# schematic.net
KiCad netlist of a schematic drawn in EAGLE
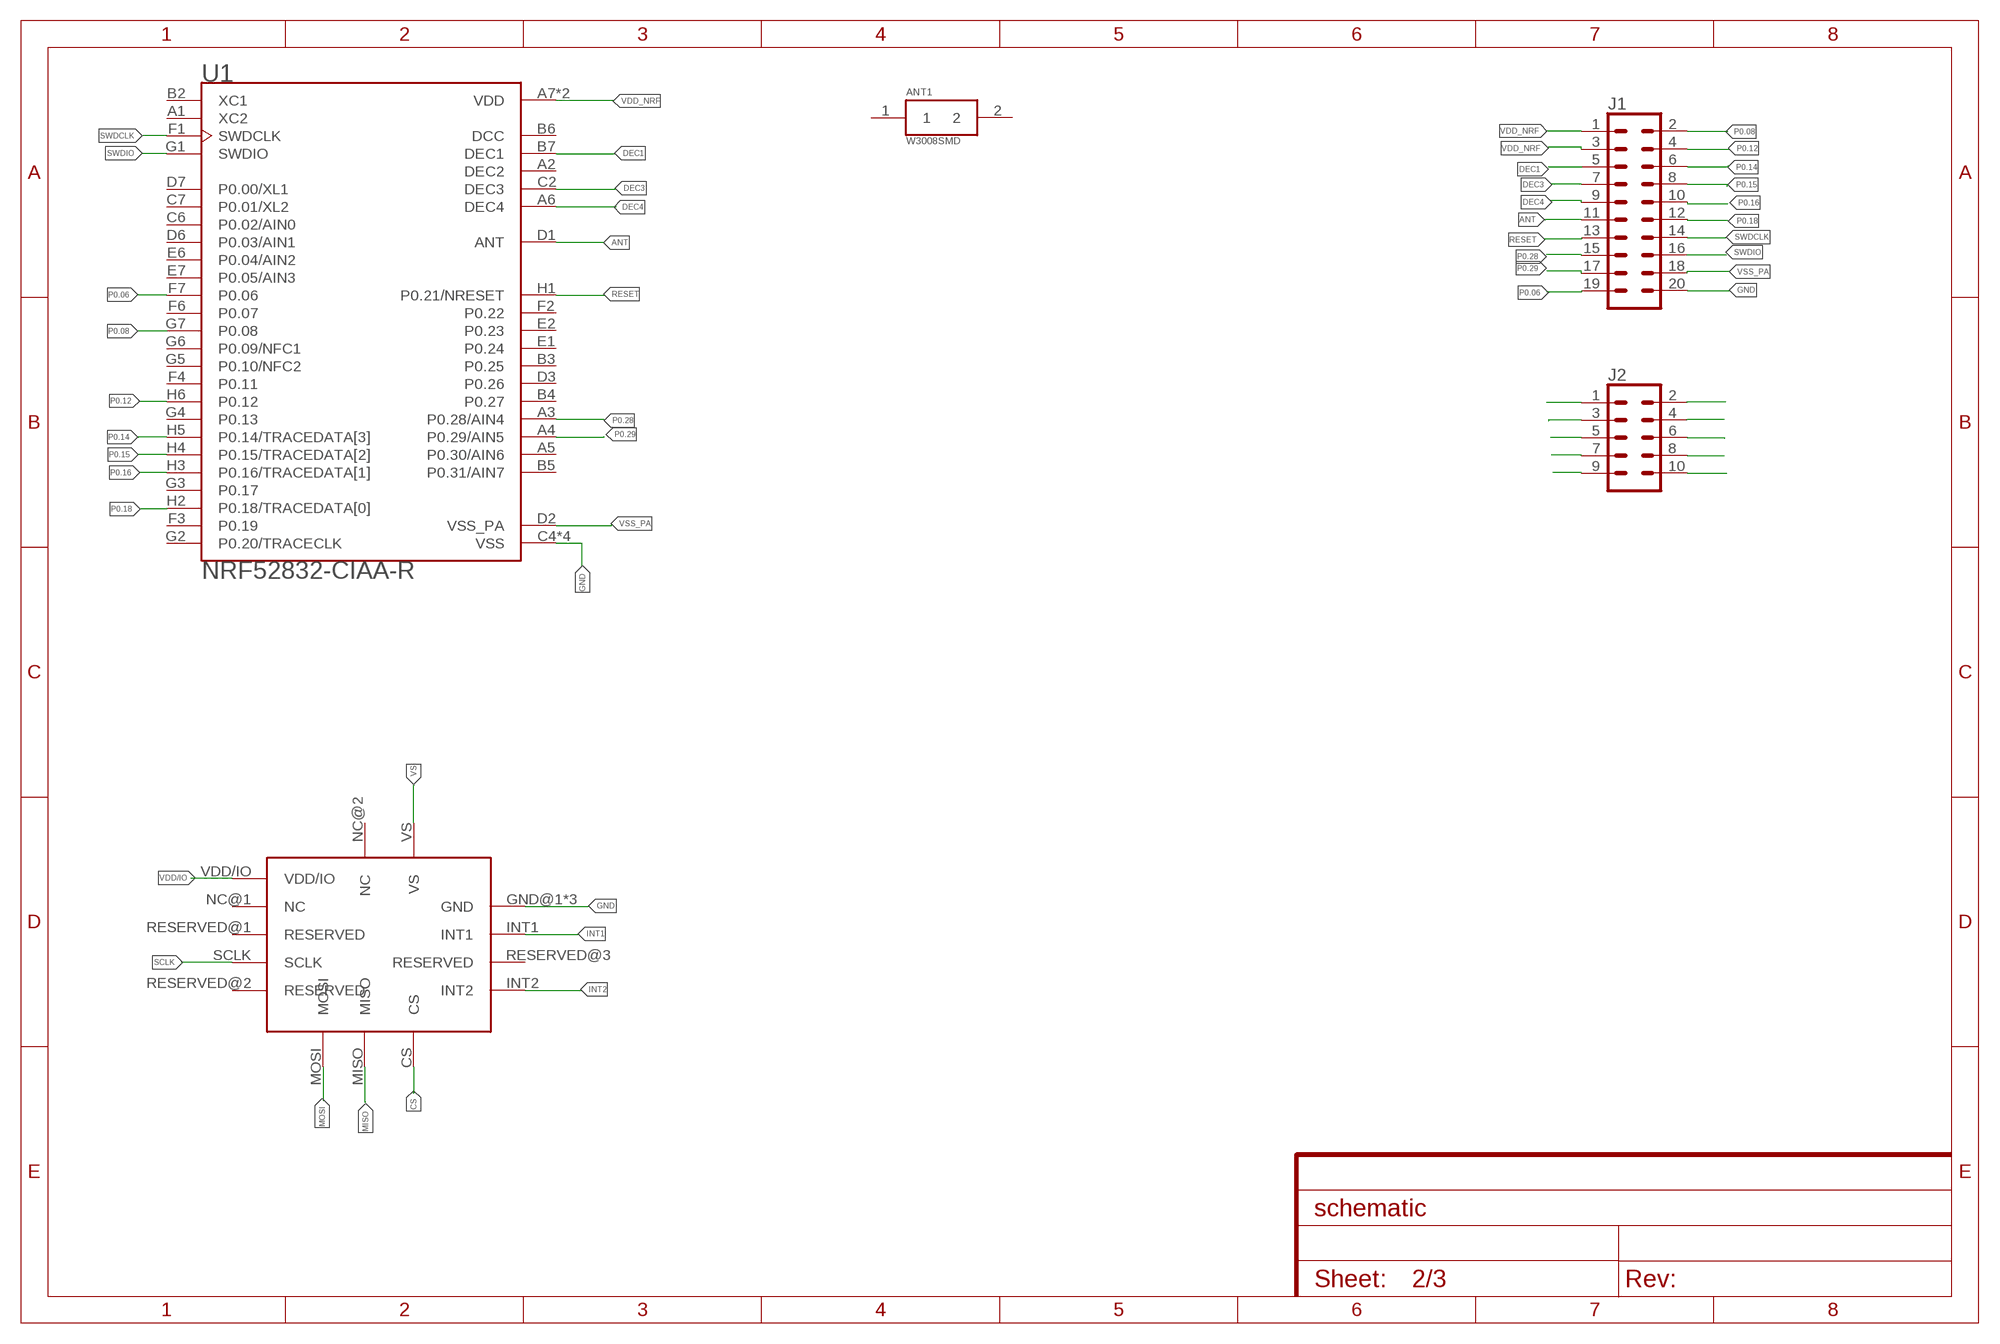
[diagram p0: schematic, sheet 2]

(export (version "E")
  (design (tool "Eeschema 10.0.6"))
  (components
    (comp (ref "ANT1")
      (value "W3008SMD")
      (footprint "eagle-import:_W3008")
      (fields (field (name "MF") "Pulse") (field (name "MP") "W3008"))
      (libsource (lib "eagle-import") (part "W3008SMD"))
    )
    (comp (ref "J1")
      (value "CONN_10X2")
      (footprint "eagle-import:2X10")
      (libsource (lib "eagle-import") (part "CONN_10X2"))
    )
    (comp (ref "J2")
      (value "CONN_05X20.05_IN_PTH_SILK")
      (footprint "eagle-import:2X5_PTH_SILK_.05")
      (libsource (lib "eagle-import") (part "CONN_05X20.05_IN_PTH_SILK"))
    )
    (comp (ref "U$1")
      (value "ADXL362")
      (footprint "eagle-import:TFLGA-16_3.3MMX3.1MM")
      (libsource (lib "eagle-import") (part "ADXL362"))
    )
    (comp (ref "U1")
      (value "NRF52832-CIAA-R")
      (footprint "eagle-import:BGA50N40P7X8_300X320X40")
      (fields (field (name "MF") "Nordic"))
      (libsource (lib "eagle-import") (part "NRF52832-CIAA-R"))
    )
  )
  (nets
    (net (code "1") (name "ANT") (class "Default")
      (node (ref "J1") (pin "11") (pinfunction "11_11") (pintype "passive"))
      (node (ref "U1") (pin "D1") (pinfunction "ANT_D1") (pintype "passive"))
    )
    (net (code "2") (name "CS") (class "Default")
      (node (ref "U$1") (pin "CS") (pinfunction "CS_CS") (pintype "bidirectional"))
    )
    (net (code "3") (name "DCC") (class "Default")
      (node (ref "U1") (pin "B6") (pinfunction "DCC_B6") (pintype "power_in"))
    )
    (net (code "4") (name "DEC1") (class "Default")
      (node (ref "J1") (pin "5") (pinfunction "5_5") (pintype "passive"))
      (node (ref "U1") (pin "B7") (pinfunction "DEC1_B7") (pintype "power_in"))
    )
    (net (code "5") (name "DEC2") (class "Default")
      (node (ref "U1") (pin "A2") (pinfunction "DEC2_A2") (pintype "power_in"))
    )
    (net (code "6") (name "DEC3") (class "Default")
      (node (ref "J1") (pin "7") (pinfunction "7_7") (pintype "passive"))
      (node (ref "U1") (pin "C2") (pinfunction "DEC3_C2") (pintype "power_in"))
    )
    (net (code "7") (name "DEC4") (class "Default")
      (node (ref "J1") (pin "9") (pinfunction "9_9") (pintype "passive"))
      (node (ref "U1") (pin "A6") (pinfunction "DEC4_A6") (pintype "power_in"))
    )
    (net (code "8") (name "GND") (class "Default")
      (node (ref "J1") (pin "20") (pinfunction "20_20") (pintype "passive"))
      (node (ref "U$1") (pin "GND@1") (pinfunction "GND_GND@1") (pintype "bidirectional"))
      (node (ref "U$1") (pin "GND@2") (pinfunction "GND_GND@2") (pintype "bidirectional"))
      (node (ref "U$1") (pin "GND@3") (pinfunction "GND_GND@3") (pintype "bidirectional"))
      (node (ref "U1") (pin "C4") (pinfunction "VSS_C4") (pintype "power_in"))
      (node (ref "U1") (pin "C5") (pinfunction "VSS_C5") (pintype "power_in"))
      (node (ref "U1") (pin "E3") (pinfunction "VSS_E3") (pintype "power_in"))
      (node (ref "U1") (pin "F5") (pinfunction "VSS_F5") (pintype "power_in"))
    )
    (net (code "9") (name "INT1") (class "Default")
      (node (ref "U$1") (pin "INT1") (pinfunction "INT1_INT1") (pintype "bidirectional"))
    )
    (net (code "10") (name "INT2") (class "Default")
      (node (ref "U$1") (pin "INT2") (pinfunction "INT2_INT2") (pintype "bidirectional"))
    )
    (net (code "11") (name "MISO") (class "Default")
      (node (ref "U$1") (pin "MISO") (pinfunction "MISO_MISO") (pintype "bidirectional"))
    )
    (net (code "12") (name "MOSI") (class "Default")
      (node (ref "U$1") (pin "MOSI") (pinfunction "MOSI_MOSI") (pintype "bidirectional"))
    )
    (net (code "13") (name "P0.06") (class "Default")
      (node (ref "J1") (pin "19") (pinfunction "19_19") (pintype "passive"))
      (node (ref "U1") (pin "F7") (pinfunction "P0.06_F7") (pintype "bidirectional"))
    )
    (net (code "14") (name "P0.08") (class "Default")
      (node (ref "J1") (pin "2") (pinfunction "2_2") (pintype "passive"))
      (node (ref "U1") (pin "G7") (pinfunction "P0.08_G7") (pintype "bidirectional"))
    )
    (net (code "15") (name "P0.12") (class "Default")
      (node (ref "J1") (pin "4") (pinfunction "4_4") (pintype "passive"))
      (node (ref "U1") (pin "H6") (pinfunction "P0.12_H6") (pintype "bidirectional"))
    )
    (net (code "16") (name "P0.14") (class "Default")
      (node (ref "J1") (pin "6") (pinfunction "6_6") (pintype "passive"))
      (node (ref "U1") (pin "H5") (pinfunction "P0.14/TRACEDATA[3]_H5") (pintype "bidirectional"))
    )
    (net (code "17") (name "P0.15") (class "Default")
      (node (ref "J1") (pin "8") (pinfunction "8_8") (pintype "passive"))
      (node (ref "U1") (pin "H4") (pinfunction "P0.15/TRACEDATA[2]_H4") (pintype "bidirectional"))
    )
    (net (code "18") (name "P0.16") (class "Default")
      (node (ref "J1") (pin "10") (pinfunction "10_10") (pintype "passive"))
      (node (ref "U1") (pin "H3") (pinfunction "P0.16/TRACEDATA[1]_H3") (pintype "bidirectional"))
    )
    (net (code "19") (name "P0.18") (class "Default")
      (node (ref "J1") (pin "12") (pinfunction "12_12") (pintype "passive"))
      (node (ref "U1") (pin "H2") (pinfunction "P0.18/TRACEDATA[0]_H2") (pintype "bidirectional"))
    )
    (net (code "20") (name "P0.28") (class "Default")
      (node (ref "J1") (pin "15") (pinfunction "15_15") (pintype "passive"))
      (node (ref "U1") (pin "A3") (pinfunction "P0.28/AIN4_A3") (pintype "bidirectional"))
    )
    (net (code "21") (name "P0.29") (class "Default")
      (node (ref "J1") (pin "17") (pinfunction "17_17") (pintype "passive"))
      (node (ref "U1") (pin "A4") (pinfunction "P0.29/AIN5_A4") (pintype "bidirectional"))
    )
    (net (code "22") (name "RESET") (class "Default")
      (node (ref "J1") (pin "13") (pinfunction "13_13") (pintype "passive"))
      (node (ref "U1") (pin "H1") (pinfunction "P0.21/NRESET_H1") (pintype "bidirectional"))
    )
    (net (code "23") (name "SCLK") (class "Default")
      (node (ref "U$1") (pin "SCLK") (pinfunction "SCLK_SCLK") (pintype "bidirectional"))
    )
    (net (code "24") (name "SWDCLK") (class "Default")
      (node (ref "J1") (pin "14") (pinfunction "14_14") (pintype "passive"))
      (node (ref "U1") (pin "F1") (pinfunction "SWDCLK_F1") (pintype "input"))
    )
    (net (code "25") (name "SWDIO") (class "Default")
      (node (ref "J1") (pin "16") (pinfunction "16_16") (pintype "passive"))
      (node (ref "U1") (pin "G1") (pinfunction "SWDIO_G1") (pintype "bidirectional"))
    )
    (net (code "26") (name "VDD_NRF") (class "Default")
      (node (ref "J1") (pin "1") (pinfunction "1_1") (pintype "passive"))
      (node (ref "J1") (pin "3") (pinfunction "3_3") (pintype "passive"))
      (node (ref "U1") (pin "A7") (pinfunction "VDD_A7") (pintype "power_in"))
      (node (ref "U1") (pin "H7") (pinfunction "VDD_H7") (pintype "power_in"))
    )
    (net (code "27") (name "VDD{slash}IO") (class "Default")
      (node (ref "U$1") (pin "VDD/IO") (pinfunction "VDD/IO_VDD/IO") (pintype "bidirectional"))
    )
    (net (code "28") (name "VS") (class "Default")
      (node (ref "U$1") (pin "VS") (pinfunction "VS_VS") (pintype "bidirectional"))
    )
    (net (code "29") (name "VSS_PA") (class "Default")
      (node (ref "J1") (pin "18") (pinfunction "18_18") (pintype "passive"))
      (node (ref "U1") (pin "D2") (pinfunction "VSS_PA_D2") (pintype "power_in"))
    )
    (net (code "30") (name "unconnected-(ANT1-Pad1)") (class "Default")
      (node (ref "ANT1") (pin "1") (pinfunction "1_1") (pintype "passive"))
    )
    (net (code "31") (name "unconnected-(ANT1-Pad2)") (class "Default")
      (node (ref "ANT1") (pin "2") (pinfunction "2_2") (pintype "passive"))
    )
    (net (code "32") (name "unconnected-(J2-Pad1)") (class "Default")
      (node (ref "J2") (pin "1") (pinfunction "1_1") (pintype "passive"))
    )
    (net (code "33") (name "unconnected-(J2-Pad2)") (class "Default")
      (node (ref "J2") (pin "2") (pinfunction "2_2") (pintype "passive"))
    )
    (net (code "34") (name "unconnected-(J2-Pad3)") (class "Default")
      (node (ref "J2") (pin "3") (pinfunction "3_3") (pintype "passive"))
    )
    (net (code "35") (name "unconnected-(J2-Pad4)") (class "Default")
      (node (ref "J2") (pin "4") (pinfunction "4_4") (pintype "passive"))
    )
    (net (code "36") (name "unconnected-(J2-Pad5)") (class "Default")
      (node (ref "J2") (pin "5") (pinfunction "5_5") (pintype "passive"))
    )
    (net (code "37") (name "unconnected-(J2-Pad6)") (class "Default")
      (node (ref "J2") (pin "6") (pinfunction "6_6") (pintype "passive"))
    )
    (net (code "38") (name "unconnected-(J2-Pad7)") (class "Default")
      (node (ref "J2") (pin "7") (pinfunction "7_7") (pintype "passive"))
    )
    (net (code "39") (name "unconnected-(J2-Pad8)") (class "Default")
      (node (ref "J2") (pin "8") (pinfunction "8_8") (pintype "passive"))
    )
    (net (code "40") (name "unconnected-(J2-Pad9)") (class "Default")
      (node (ref "J2") (pin "9") (pinfunction "9_9") (pintype "passive"))
    )
    (net (code "41") (name "unconnected-(J2-Pad10)") (class "Default")
      (node (ref "J2") (pin "10") (pinfunction "10_10") (pintype "passive"))
    )
    (net (code "42") (name "unconnected-(U$1-NC-PadNC@1)") (class "Default")
      (node (ref "U$1") (pin "NC@1") (pinfunction "NC_NC@1") (pintype "bidirectional"))
    )
    (net (code "43") (name "unconnected-(U$1-NC-PadNC@2)") (class "Default")
      (node (ref "U$1") (pin "NC@2") (pinfunction "NC_NC@2") (pintype "bidirectional"))
    )
    (net (code "44") (name "unconnected-(U$1-RESERVED-PadRESERVED@1)") (class "Default")
      (node (ref "U$1") (pin "RESERVED@1") (pinfunction "RESERVED_RESERVED@1") (pintype "bidirectional"))
    )
    (net (code "45") (name "unconnected-(U$1-RESERVED-PadRESERVED@2)") (class "Default")
      (node (ref "U$1") (pin "RESERVED@2") (pinfunction "RESERVED_RESERVED@2") (pintype "bidirectional"))
    )
    (net (code "46") (name "unconnected-(U$1-RESERVED-PadRESERVED@3)") (class "Default")
      (node (ref "U$1") (pin "RESERVED@3") (pinfunction "RESERVED_RESERVED@3") (pintype "bidirectional"))
    )
    (net (code "47") (name "unconnected-(U1-P0.00{slash}XL1-PadD7)") (class "Default")
      (node (ref "U1") (pin "D7") (pinfunction "P0.00/XL1_D7") (pintype "bidirectional"))
    )
    (net (code "48") (name "unconnected-(U1-P0.01{slash}XL2-PadC7)") (class "Default")
      (node (ref "U1") (pin "C7") (pinfunction "P0.01/XL2_C7") (pintype "bidirectional"))
    )
    (net (code "49") (name "unconnected-(U1-P0.02{slash}AIN0-PadC6)") (class "Default")
      (node (ref "U1") (pin "C6") (pinfunction "P0.02/AIN0_C6") (pintype "bidirectional"))
    )
    (net (code "50") (name "unconnected-(U1-P0.03{slash}AIN1-PadD6)") (class "Default")
      (node (ref "U1") (pin "D6") (pinfunction "P0.03/AIN1_D6") (pintype "bidirectional"))
    )
    (net (code "51") (name "unconnected-(U1-P0.04{slash}AIN2-PadE6)") (class "Default")
      (node (ref "U1") (pin "E6") (pinfunction "P0.04/AIN2_E6") (pintype "bidirectional"))
    )
    (net (code "52") (name "unconnected-(U1-P0.05{slash}AIN3-PadE7)") (class "Default")
      (node (ref "U1") (pin "E7") (pinfunction "P0.05/AIN3_E7") (pintype "bidirectional"))
    )
    (net (code "53") (name "unconnected-(U1-P0.07-PadF6)") (class "Default")
      (node (ref "U1") (pin "F6") (pinfunction "P0.07_F6") (pintype "bidirectional"))
    )
    (net (code "54") (name "unconnected-(U1-P0.09{slash}NFC1-PadG6)") (class "Default")
      (node (ref "U1") (pin "G6") (pinfunction "P0.09/NFC1_G6") (pintype "bidirectional"))
    )
    (net (code "55") (name "unconnected-(U1-P0.10{slash}NFC2-PadG5)") (class "Default")
      (node (ref "U1") (pin "G5") (pinfunction "P0.10/NFC2_G5") (pintype "bidirectional"))
    )
    (net (code "56") (name "unconnected-(U1-P0.11-PadF4)") (class "Default")
      (node (ref "U1") (pin "F4") (pinfunction "P0.11_F4") (pintype "bidirectional"))
    )
    (net (code "57") (name "unconnected-(U1-P0.13-PadG4)") (class "Default")
      (node (ref "U1") (pin "G4") (pinfunction "P0.13_G4") (pintype "bidirectional"))
    )
    (net (code "58") (name "unconnected-(U1-P0.17-PadG3)") (class "Default")
      (node (ref "U1") (pin "G3") (pinfunction "P0.17_G3") (pintype "bidirectional"))
    )
    (net (code "59") (name "unconnected-(U1-P0.19-PadF3)") (class "Default")
      (node (ref "U1") (pin "F3") (pinfunction "P0.19_F3") (pintype "bidirectional"))
    )
    (net (code "60") (name "unconnected-(U1-P0.20{slash}TRACECLK-PadG2)") (class "Default")
      (node (ref "U1") (pin "G2") (pinfunction "P0.20/TRACECLK_G2") (pintype "bidirectional"))
    )
    (net (code "61") (name "unconnected-(U1-P0.22-PadF2)") (class "Default")
      (node (ref "U1") (pin "F2") (pinfunction "P0.22_F2") (pintype "bidirectional"))
    )
    (net (code "62") (name "unconnected-(U1-P0.23-PadE2)") (class "Default")
      (node (ref "U1") (pin "E2") (pinfunction "P0.23_E2") (pintype "bidirectional"))
    )
    (net (code "63") (name "unconnected-(U1-P0.24-PadE1)") (class "Default")
      (node (ref "U1") (pin "E1") (pinfunction "P0.24_E1") (pintype "bidirectional"))
    )
    (net (code "64") (name "unconnected-(U1-P0.25-PadB3)") (class "Default")
      (node (ref "U1") (pin "B3") (pinfunction "P0.25_B3") (pintype "bidirectional"))
    )
    (net (code "65") (name "unconnected-(U1-P0.26-PadD3)") (class "Default")
      (node (ref "U1") (pin "D3") (pinfunction "P0.26_D3") (pintype "bidirectional"))
    )
    (net (code "66") (name "unconnected-(U1-P0.27-PadB4)") (class "Default")
      (node (ref "U1") (pin "B4") (pinfunction "P0.27_B4") (pintype "bidirectional"))
    )
    (net (code "67") (name "unconnected-(U1-P0.30{slash}AIN6-PadA5)") (class "Default")
      (node (ref "U1") (pin "A5") (pinfunction "P0.30/AIN6_A5") (pintype "bidirectional"))
    )
    (net (code "68") (name "unconnected-(U1-P0.31{slash}AIN7-PadB5)") (class "Default")
      (node (ref "U1") (pin "B5") (pinfunction "P0.31/AIN7_B5") (pintype "bidirectional"))
    )
    (net (code "69") (name "unconnected-(U1-XC1-PadB2)") (class "Default")
      (node (ref "U1") (pin "B2") (pinfunction "XC1_B2") (pintype "input"))
    )
    (net (code "70") (name "unconnected-(U1-XC2-PadA1)") (class "Default")
      (node (ref "U1") (pin "A1") (pinfunction "XC2_A1") (pintype "input"))
    )
  )
)
